# dental-unit-main_v1_0.net
KiCad netlist of a schematic drawn in Altium Designer
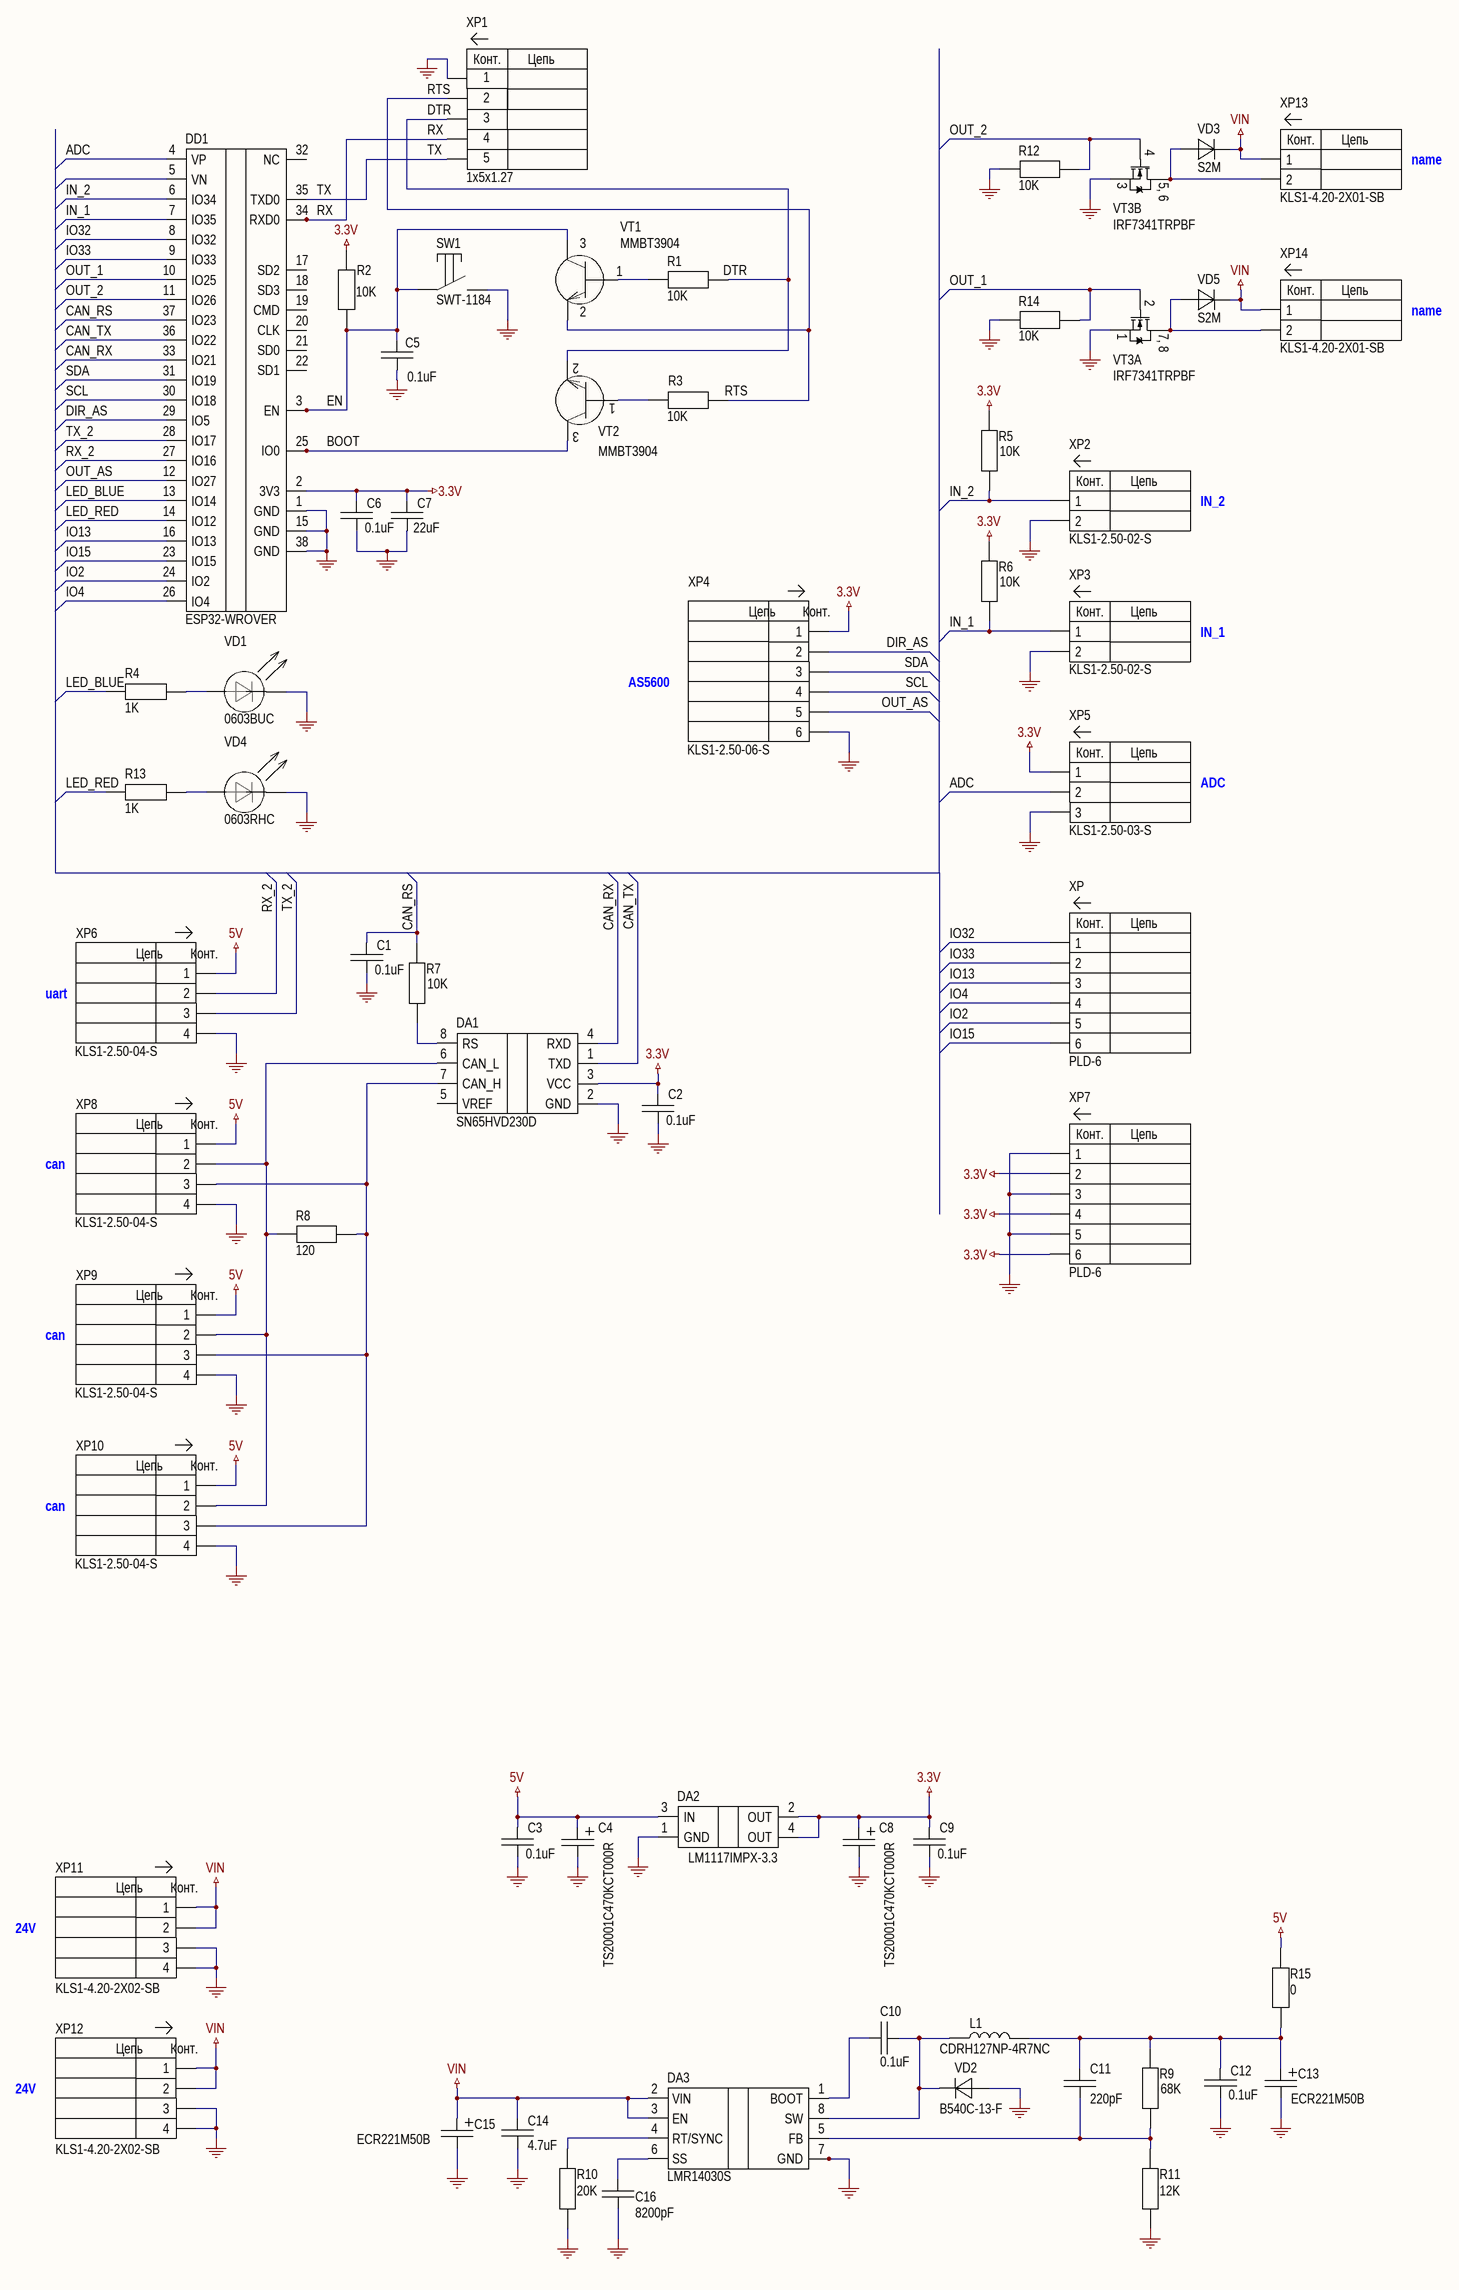
[diagram p0: dental-unit-main v1_0.SchDoc]

(export (version "E")
  (design (tool "Eeschema 10.0.6"))
  (components
    (comp (ref "C1")
      (value "0.1uF")
      (footprint "CC_0603")
      (description "Cap Ceramic, 0603, 0.1u, 10%, 16V, X7R (Yageo)")
      (fields (field (name "Comment") "CC0603KRX7R5BB104"))
      (libsource (lib "my_discrete_new") (part "C"))
    )
    (comp (ref "C2")
      (value "0.1uF")
      (footprint "CC_0603")
      (description "Cap Ceramic, 0603, 0.1u, 10%, 16V, X7R (Yageo)")
      (fields (field (name "Comment") "CC0603KRX7R5BB104"))
      (libsource (lib "my_discrete_new") (part "C"))
    )
    (comp (ref "C3")
      (value "0.1uF")
      (footprint "CC_0603")
      (description "Cap Ceramic, 0603, 0.1u, 10%, 16V, X7R (Yageo)")
      (fields (field (name "Comment") "CC0603KRX7R5BB104"))
      (libsource (lib "my_discrete_new") (part "C"))
    )
    (comp (ref "C4")
      (value "TS20001C470KCT000R")
      (footprint "CC_TANT_C")
      (description "47uF, 16v, C, 10%, @SUNTAN,")
      (libsource (lib "my_discrete_new") (part "C_polar"))
    )
    (comp (ref "C5")
      (value "0.1uF")
      (footprint "CC_0603")
      (description "Cap Ceramic, 0603, 0.1u, 10%, 16V, X7R (Yageo)")
      (fields (field (name "Comment") "CC0603KRX7R5BB104"))
      (libsource (lib "my_discrete_new") (part "C"))
    )
    (comp (ref "C6")
      (value "0.1uF")
      (footprint "CC_0603")
      (description "Cap Ceramic, 0603, 0.1u, 10%, 16V, X7R (Yageo)")
      (fields (field (name "Comment") "CC0603KRX7R5BB104"))
      (libsource (lib "my_discrete_new") (part "C"))
    )
    (comp (ref "C7")
      (value "22uF")
      (footprint "CC_0805")
      (description "Cap Ceramic, 0805, 22u, 20%, 6.3V, X5R, -55 +85C (Murata)")
      (fields (field (name "Comment") "GRM21BR60J226ME39L"))
      (libsource (lib "my_discrete_new") (part "C"))
    )
    (comp (ref "C8")
      (value "TS20001C470KCT000R")
      (footprint "CC_TANT_C")
      (description "47uF, 16v, C, 10%, @SUNTAN,")
      (libsource (lib "my_discrete_new") (part "C_polar"))
    )
    (comp (ref "C9")
      (value "0.1uF")
      (footprint "CC_0603")
      (description "Cap Ceramic, 0603, 0.1u, 10%, 16V, X7R (Yageo)")
      (fields (field (name "Comment") "CC0603KRX7R5BB104"))
      (libsource (lib "my_discrete_new") (part "C"))
    )
    (comp (ref "C10")
      (value "0.1uF")
      (footprint "CC_0805")
      (description "Cap Ceramic, 0805, 0.1u, 5%, 50V, X7R (Yageo)")
      (fields (field (name "Comment") "CC0805JRX7R9BB104"))
      (libsource (lib "my_discrete_new") (part "C"))
    )
    (comp (ref "C11")
      (value "220pF")
      (footprint "CC_0603")
      (description "Cap Ceramic, 0603, 220pF, 10%, 50V, NP0, @YAGEO")
      (fields (field (name "Comment") "CC0603KRX7R9BB221"))
      (libsource (lib "my_discrete_new") (part "C"))
    )
    (comp (ref "C12")
      (value "0.1uF")
      (footprint "CC_0603")
      (description "Cap Ceramic, 0603, 0.1u, 10%, 16V, X7R (Yageo)")
      (fields (field (name "Comment") "CC0603KRX7R5BB104"))
      (libsource (lib "my_discrete_new") (part "C"))
    )
    (comp (ref "C13")
      (value "ECR221M50B")
      (footprint "C_ele_10x13")
      (description "alum. el. Cap, 50v, 220u, 20%, 13x20, @HITANO")
      (libsource (lib "my_discrete_new") (part "C_polar"))
    )
    (comp (ref "C14")
      (value "4.7uF")
      (footprint "CC_0603")
      (description "Cap Ceramic, 0603, 4.7u, 10%, 25V, X5R (Sumsung)")
      (fields (field (name "Comment") "CL10A475KA8NQNC"))
      (libsource (lib "my_discrete_new") (part "C"))
    )
    (comp (ref "C15")
      (value "ECR221M50B")
      (footprint "C_ele_10x13")
      (description "alum. el. Cap, 50v, 220u, 20%, 13x20, @HITANO")
      (libsource (lib "my_discrete_new") (part "C_polar"))
    )
    (comp (ref "C16")
      (value "8200pF")
      (footprint "CC_0603")
      (description "Cap Ceramic, 0603, 8200pF, 10%, 50V, X7R (Yageo)")
      (fields (field (name "Comment") "CC0603KRX7R9BB822"))
      (libsource (lib "my_discrete_new") (part "C"))
    )
    (comp (ref "DA1")
      (value "SN65HVD230D")
      (footprint "SOIC-8")
      (description "3.3-V CAN TRANSCEIVERS, @TI")
      (libsource (lib "my_microschems_new") (part "SN65HVD230D"))
    )
    (comp (ref "DA2")
      (value "LM1117IMPX-3.3")
      (footprint "SOT-223")
      (description "LDO, 3.3v, 0.8A, SOT-223, Texas Instruments")
      (libsource (lib "my_microschems_new") (part "LM1117IMPX-3.3"))
    )
    (comp (ref "DA3")
      (value "LMR14030S")
      (footprint "SOIC-8N")
      (description "DC-DC Step-Down Converter, 40V, 3.5A, @TI")
      (libsource (lib "my_microschems_new") (part "LMR14030S"))
    )
    (comp (ref "DD1")
      (value "ESP32-WROVER")
      (footprint "ESP32-WROVER / WROOM")
      (libsource (lib "my_microschems_new") (part "ESP32-WROVER"))
    )
    (comp (ref "L1")
      (value "CDRH127NP-4R7NC")
      (footprint "CDRH127NP")
      (description "4.7uH, 6.8A, @SUMIDA")
      (libsource (lib "my_discrete_new") (part "L"))
    )
    (comp (ref "R1")
      (value "10K")
      (footprint "RC_0603")
      (description "Res, 0603, 10K, 1%, 0.25W (ф. Yageo)")
      (fields (field (name "POWER") "0.25W") (field (name "Comment") "AC0603FR-0710KL"))
      (libsource (lib "my_discrete_new") (part "R"))
    )
    (comp (ref "R2")
      (value "10K")
      (footprint "RC_0603")
      (description "Res, 0603, 10K, 1%, 0.25W (ф. Yageo)")
      (fields (field (name "POWER") "0.25W") (field (name "Comment") "AC0603FR-0710KL"))
      (libsource (lib "my_discrete_new") (part "R"))
    )
    (comp (ref "R3")
      (value "10K")
      (footprint "RC_0603")
      (description "Res, 0603, 10K, 1%, 0.25W (ф. Yageo)")
      (fields (field (name "POWER") "0.25W") (field (name "Comment") "AC0603FR-0710KL"))
      (libsource (lib "my_discrete_new") (part "R"))
    )
    (comp (ref "R4")
      (value "1K")
      (footprint "RC_0603")
      (description "Res, 0603, 1K 1%, 0.25W (ф. Yageo)")
      (fields (field (name "POWER") "0.25W") (field (name "Comment") "AC0603FR-071KL"))
      (libsource (lib "my_discrete_new") (part "R"))
    )
    (comp (ref "R5")
      (value "10K")
      (footprint "RC_0603")
      (description "Res, 0603, 10K, 1%, 0.25W (ф. Yageo)")
      (fields (field (name "POWER") "0.25W") (field (name "Comment") "AC0603FR-0710KL"))
      (libsource (lib "my_discrete_new") (part "R"))
    )
    (comp (ref "R6")
      (value "10K")
      (footprint "RC_0603")
      (description "Res, 0603, 10K, 1%, 0.25W (ф. Yageo)")
      (fields (field (name "POWER") "0.25W") (field (name "Comment") "AC0603FR-0710KL"))
      (libsource (lib "my_discrete_new") (part "R"))
    )
    (comp (ref "R7")
      (value "10K")
      (footprint "RC_0603")
      (description "Res, 0603, 10K, 1%, 0.25W (ф. Yageo)")
      (fields (field (name "POWER") "0.25W") (field (name "Comment") "AC0603FR-0710KL"))
      (libsource (lib "my_discrete_new") (part "R"))
    )
    (comp (ref "R8")
      (value "120")
      (footprint "RC_0603")
      (description "Res, 0603, 120, 1%, 0.25W (ф. Yageo)")
      (fields (field (name "POWER") "0.25W") (field (name "Comment") "RC0603FR-07120RL"))
      (libsource (lib "my_discrete_new") (part "R"))
    )
    (comp (ref "R9")
      (value "68K")
      (footprint "RC_0603")
      (description "Res, 0603, 68K, 1%, 0.25W (ф. Yageo)")
      (fields (field (name "POWER") "0.25W") (field (name "Comment") "RC0603FR-0768KL"))
      (libsource (lib "my_discrete_new") (part "R"))
    )
    (comp (ref "R10")
      (value "20K")
      (footprint "RC_0603")
      (description "Res, 0603, 20K, 1%, 0.25W (ф. Yageo)")
      (fields (field (name "POWER") "0.25W") (field (name "Comment") "RC0603FR-0720KL"))
      (libsource (lib "my_discrete_new") (part "R"))
    )
    (comp (ref "R11")
      (value "12K")
      (footprint "RC_0603")
      (description "Res, 0603, 12K, 1%, 0.25W (ф. Yageo)")
      (fields (field (name "POWER") "0.25W") (field (name "Comment") "RC0603FR-0712KL"))
      (libsource (lib "my_discrete_new") (part "R"))
    )
    (comp (ref "R12")
      (value "10K")
      (footprint "RC_0603")
      (description "Res, 0603, 10K, 1%, 0.25W (ф. Yageo)")
      (fields (field (name "POWER") "0.25W") (field (name "Comment") "AC0603FR-0710KL"))
      (libsource (lib "my_discrete_new") (part "R"))
    )
    (comp (ref "R13")
      (value "1K")
      (footprint "RC_0603")
      (description "Res, 0603, 1K 1%, 0.25W (ф. Yageo)")
      (fields (field (name "POWER") "0.25W") (field (name "Comment") "AC0603FR-071KL"))
      (libsource (lib "my_discrete_new") (part "R"))
    )
    (comp (ref "R14")
      (value "10K")
      (footprint "RC_0603")
      (description "Res, 0603, 10K, 1%, 0.25W (ф. Yageo)")
      (fields (field (name "POWER") "0.25W") (field (name "Comment") "AC0603FR-0710KL"))
      (libsource (lib "my_discrete_new") (part "R"))
    )
    (comp (ref "R15")
      (value "0")
      (footprint "RC_0603")
      (description "Res, 0603, 0, 1%, 0.25W (ф. Yageo)")
      (fields (field (name "POWER") "0.25W") (field (name "Comment") "AC0603FR-070RL"))
      (libsource (lib "my_discrete_new") (part "R"))
    )
    (comp (ref "SW1")
      (value "SWT-1184")
      (footprint "IT-1184")
      (libsource (lib "my_discrete_new") (part "smd-side-push-button"))
    )
    (comp (ref "VD1")
      (value "0603BUC")
      (footprint "LED_0603")
      (description "Led, 0603, BLUE, 20mA, 125, 140MCD, CPMELEC")
      (libsource (lib "my_discrete_new") (part "LED"))
    )
    (comp (ref "VD2")
      (value "B540C-13-F")
      (footprint "DO-214AB(SMC)")
      (libsource (lib "my_discrete_new") (part "D"))
    )
    (comp (ref "VD3")
      (value "S2M")
      (footprint "DO-214AA(SMB)")
      (description "1000В, 2А, 2,5мкс, SMB, @DIODES")
      (libsource (lib "my_discrete_new") (part "D"))
    )
    (comp (ref "VD4")
      (value "0603RHC")
      (footprint "LED_0603")
      (description "Led, 0603, RED, 20mA, 125, 140MCD, CPMELEC")
      (libsource (lib "my_discrete_new") (part "LED"))
    )
    (comp (ref "VD5")
      (value "S2M")
      (footprint "DO-214AA(SMB)")
      (description "1000В, 2А, 2,5мкс, SMB, @DIODES")
      (libsource (lib "my_discrete_new") (part "D"))
    )
    (comp (ref "VT1")
      (value "MMBT3904")
      (footprint "SOT-23-3")
      (libsource (lib "my_microschems_new") (part "N-P-N-SOT-23"))
    )
    (comp (ref "VT2")
      (value "MMBT3904")
      (footprint "SOT-23-3")
      (libsource (lib "my_microschems_new") (part "N-P-N-SOT-23"))
    )
    (comp (ref "VT3")
      (value "IRF7341TRPBF")
      (footprint "SOIC-8")
      (description "HEXFET Power MOSFET, Dual N-Channel Mosfet, 55 В, 4.7 А, 2 Вт, @INFIN")
      (libsource (lib "my_microschems_new") (part "IRF7341TRPBF"))
    )
    (comp (ref "XP")
      (value "PLD-6")
      (footprint "PLD-6")
      (libsource (lib "my_connectors_new") (part "XT_PLD-6"))
    )
    (comp (ref "XP1")
      (value "1x5x1.27")
      (footprint "XT_1x5x1.27_offset")
      (libsource (lib "my_connectors_new") (part "XT_1x5x1_27"))
    )
    (comp (ref "XP2")
      (value "KLS1-2.50-02-S")
      (footprint "KLS1-2.50-02-S")
      (description "2.5mm, 2pin, KLS")
      (fields (field (name "NAME") "IN_2"))
      (libsource (lib "my_connectors_new") (part "KLS1-2.50-02-x"))
    )
    (comp (ref "XP3")
      (value "KLS1-2.50-02-S")
      (footprint "KLS1-2.50-02-S")
      (description "2.5mm, 2pin, KLS")
      (fields (field (name "NAME") "IN_1"))
      (libsource (lib "my_connectors_new") (part "KLS1-2.50-02-x"))
    )
    (comp (ref "XP4")
      (value "KLS1-2.50-06-S")
      (footprint "KLS1-2.50-06-S")
      (description "2.5mm, 6pin, KLS")
      (fields (field (name "NAME") "AS5600"))
      (libsource (lib "my_connectors_new") (part "KLS1-2.50-06-x"))
    )
    (comp (ref "XP5")
      (value "KLS1-2.50-03-S")
      (footprint "KLS1-2.50-03-S")
      (description "2.5mm, 3pin, KLS")
      (fields (field (name "NAME") "ADC"))
      (libsource (lib "my_connectors_new") (part "KLS1-2.50-03-x"))
    )
    (comp (ref "XP6")
      (value "KLS1-2.50-04-S")
      (footprint "KLS1-2.50-04-S")
      (description "2.5mm, 4pin, KLS")
      (fields (field (name "NAME") "uart"))
      (libsource (lib "my_connectors_new") (part "KLS1-2.50-04-x"))
    )
    (comp (ref "XP7")
      (value "PLD-6")
      (footprint "PLD-6")
      (libsource (lib "my_connectors_new") (part "XT_PLD-6"))
    )
    (comp (ref "XP8")
      (value "KLS1-2.50-04-S")
      (footprint "KLS1-2.50-04-S")
      (description "2.5mm, 4pin, KLS")
      (fields (field (name "NAME") "can"))
      (libsource (lib "my_connectors_new") (part "KLS1-2.50-04-x"))
    )
    (comp (ref "XP9")
      (value "KLS1-2.50-04-S")
      (footprint "KLS1-2.50-04-S")
      (description "2.5mm, 4pin, KLS")
      (fields (field (name "NAME") "can"))
      (libsource (lib "my_connectors_new") (part "KLS1-2.50-04-x"))
    )
    (comp (ref "XP10")
      (value "KLS1-2.50-04-S")
      (footprint "KLS1-2.50-04-S")
      (description "2.5mm, 4pin, KLS")
      (fields (field (name "NAME") "can"))
      (libsource (lib "my_connectors_new") (part "KLS1-2.50-04-x"))
    )
    (comp (ref "XP11")
      (value "KLS1-4.20-2X02-SB")
      (footprint "KLS1-4.20-2X02-SB")
      (description "4.2mm, 4pin, KLS")
      (fields (field (name "NAME") "24V"))
      (libsource (lib "my_connectors_new") (part "KLS1-4.20-2X02-x"))
    )
    (comp (ref "XP12")
      (value "KLS1-4.20-2X02-SB")
      (footprint "KLS1-4.20-2X02-SB")
      (description "4.2mm, 4pin, KLS")
      (fields (field (name "NAME") "24V"))
      (libsource (lib "my_connectors_new") (part "KLS1-4.20-2X02-x"))
    )
    (comp (ref "XP13")
      (value "KLS1-4.20-2X01-SB")
      (footprint "KLS1-4.20-2X01-SB")
      (description "4.2mm, 2pin, KLS")
      (fields (field (name "NAME") "name"))
      (libsource (lib "my_connectors_new") (part "KLS1-4.20-2X01-x"))
    )
    (comp (ref "XP14")
      (value "KLS1-4.20-2X01-SB")
      (footprint "KLS1-4.20-2X01-SB")
      (description "4.2mm, 2pin, KLS")
      (fields (field (name "NAME") "name"))
      (libsource (lib "my_connectors_new") (part "KLS1-4.20-2X01-x"))
    )
  )
  (nets
    (net (code "1") (name "/ADC") (class "Default")
      (node (ref "DD1") (pin "4") (pinfunction "VP_4") (pintype "passive"))
      (node (ref "XP5") (pin "2") (pinfunction "2_2") (pintype "passive"))
    )
    (net (code "2") (name "/BOOT") (class "Default")
      (node (ref "DD1") (pin "25") (pinfunction "IO0_25") (pintype "passive"))
      (node (ref "VT2") (pin "3") (pinfunction "C_3") (pintype "passive"))
    )
    (net (code "3") (name "/CAN_RS") (class "Default")
      (node (ref "C1") (pin "2") (pinfunction "2_2") (pintype "passive"))
      (node (ref "DD1") (pin "37") (pinfunction "IO23_37") (pintype "passive"))
      (node (ref "R7") (pin "2") (pinfunction "2_2") (pintype "passive"))
    )
    (net (code "4") (name "/CAN_RX") (class "Default")
      (node (ref "DA1") (pin "4") (pinfunction "RXD_4") (pintype "power_in"))
      (node (ref "DD1") (pin "33") (pinfunction "IO21_33") (pintype "passive"))
    )
    (net (code "5") (name "/CAN_TX") (class "Default")
      (node (ref "DA1") (pin "1") (pinfunction "TXD_1") (pintype "passive"))
      (node (ref "DD1") (pin "36") (pinfunction "IO22_36") (pintype "passive"))
    )
    (net (code "6") (name "/DIR_AS") (class "Default")
      (node (ref "DD1") (pin "29") (pinfunction "IO5_29") (pintype "passive"))
      (node (ref "XP4") (pin "2") (pinfunction "2_2") (pintype "passive"))
    )
    (net (code "7") (name "/DTR") (class "Default")
      (node (ref "R1") (pin "2") (pinfunction "2_2") (pintype "passive"))
      (node (ref "VT2") (pin "2") (pinfunction "E_2") (pintype "passive"))
      (node (ref "XP1") (pin "3") (pinfunction "3_3") (pintype "passive"))
    )
    (net (code "8") (name "/EN") (class "Default")
      (node (ref "C5") (pin "2") (pinfunction "2_2") (pintype "passive"))
      (node (ref "DD1") (pin "3") (pinfunction "EN_3") (pintype "passive"))
      (node (ref "R2") (pin "1") (pinfunction "1_1") (pintype "passive"))
      (node (ref "SW1") (pin "1") (pinfunction "1_1") (pintype "passive"))
      (node (ref "VT1") (pin "3") (pinfunction "C_3") (pintype "passive"))
    )
    (net (code "9") (name "/IN_1") (class "Default")
      (node (ref "DD1") (pin "7") (pinfunction "IO35_7") (pintype "passive"))
      (node (ref "R6") (pin "1") (pinfunction "1_1") (pintype "passive"))
      (node (ref "XP3") (pin "1") (pinfunction "1_1") (pintype "passive"))
    )
    (net (code "10") (name "/IN_2") (class "Default")
      (node (ref "DD1") (pin "6") (pinfunction "IO34_6") (pintype "passive"))
      (node (ref "R5") (pin "1") (pinfunction "1_1") (pintype "passive"))
      (node (ref "XP2") (pin "1") (pinfunction "1_1") (pintype "passive"))
    )
    (net (code "11") (name "/IO2") (class "Default")
      (node (ref "DD1") (pin "24") (pinfunction "IO2_24") (pintype "passive"))
      (node (ref "XP") (pin "5") (pinfunction "5_5") (pintype "passive"))
    )
    (net (code "12") (name "/IO4") (class "Default")
      (node (ref "DD1") (pin "26") (pinfunction "IO4_26") (pintype "passive"))
      (node (ref "XP") (pin "4") (pinfunction "4_4") (pintype "passive"))
    )
    (net (code "13") (name "/IO13") (class "Default")
      (node (ref "DD1") (pin "16") (pinfunction "IO13_16") (pintype "passive"))
      (node (ref "XP") (pin "3") (pinfunction "3_3") (pintype "passive"))
    )
    (net (code "14") (name "/IO15") (class "Default")
      (node (ref "DD1") (pin "23") (pinfunction "IO15_23") (pintype "passive"))
      (node (ref "XP") (pin "6") (pinfunction "6_6") (pintype "passive"))
    )
    (net (code "15") (name "/IO32") (class "Default")
      (node (ref "DD1") (pin "8") (pinfunction "IO32_8") (pintype "power_in"))
      (node (ref "XP") (pin "1") (pinfunction "1_1") (pintype "passive"))
    )
    (net (code "16") (name "/IO33") (class "Default")
      (node (ref "DD1") (pin "9") (pinfunction "IO33_9") (pintype "passive"))
      (node (ref "XP") (pin "2") (pinfunction "2_2") (pintype "passive"))
    )
    (net (code "17") (name "/LED_BLUE") (class "Default")
      (node (ref "DD1") (pin "13") (pinfunction "IO14_13") (pintype "passive"))
      (node (ref "R4") (pin "1") (pinfunction "1_1") (pintype "passive"))
    )
    (net (code "18") (name "/LED_RED") (class "Default")
      (node (ref "DD1") (pin "14") (pinfunction "IO12_14") (pintype "passive"))
      (node (ref "R13") (pin "1") (pinfunction "1_1") (pintype "passive"))
    )
    (net (code "19") (name "/OUT_1") (class "Default")
      (node (ref "DD1") (pin "10") (pinfunction "IO25_10") (pintype "passive"))
      (node (ref "R14") (pin "1") (pinfunction "1_1") (pintype "passive"))
      (node (ref "VT3") (pin "2") (pinfunction "G_2") (pintype "passive"))
    )
    (net (code "20") (name "/OUT_2") (class "Default")
      (node (ref "DD1") (pin "11") (pinfunction "IO26_11") (pintype "passive"))
      (node (ref "R12") (pin "1") (pinfunction "1_1") (pintype "passive"))
      (node (ref "VT3") (pin "4") (pinfunction "G_4") (pintype "passive"))
    )
    (net (code "21") (name "/OUT_AS") (class "Default")
      (node (ref "DD1") (pin "12") (pinfunction "IO27_12") (pintype "passive"))
      (node (ref "XP4") (pin "5") (pinfunction "5_5") (pintype "passive"))
    )
    (net (code "22") (name "/RTS") (class "Default")
      (node (ref "R3") (pin "2") (pinfunction "2_2") (pintype "passive"))
      (node (ref "VT1") (pin "2") (pinfunction "E_2") (pintype "passive"))
      (node (ref "XP1") (pin "2") (pinfunction "2_2") (pintype "passive"))
    )
    (net (code "23") (name "/RX") (class "Default")
      (node (ref "DD1") (pin "34") (pinfunction "RXD0_34") (pintype "passive"))
      (node (ref "XP1") (pin "4") (pinfunction "4_4") (pintype "passive"))
    )
    (net (code "24") (name "/RX_2") (class "Default")
      (node (ref "DD1") (pin "27") (pinfunction "IO16_27") (pintype "passive"))
      (node (ref "XP6") (pin "2") (pinfunction "2_2") (pintype "passive"))
    )
    (net (code "25") (name "/SCL") (class "Default")
      (node (ref "DD1") (pin "30") (pinfunction "IO18_30") (pintype "passive"))
      (node (ref "XP4") (pin "4") (pinfunction "4_4") (pintype "passive"))
    )
    (net (code "26") (name "/SDA") (class "Default")
      (node (ref "DD1") (pin "31") (pinfunction "IO19_31") (pintype "passive"))
      (node (ref "XP4") (pin "3") (pinfunction "3_3") (pintype "passive"))
    )
    (net (code "27") (name "/TX") (class "Default")
      (node (ref "DD1") (pin "35") (pinfunction "TXD0_35") (pintype "passive"))
      (node (ref "XP1") (pin "5") (pinfunction "5_5") (pintype "passive"))
    )
    (net (code "28") (name "/TX_2") (class "Default")
      (node (ref "DD1") (pin "28") (pinfunction "IO17_28") (pintype "passive"))
      (node (ref "XP6") (pin "3") (pinfunction "3_3") (pintype "passive"))
    )
    (net (code "29") (name "3.3V") (class "Default")
      (node (ref "C2") (pin "2") (pinfunction "2_2") (pintype "passive"))
      (node (ref "C6") (pin "2") (pinfunction "2_2") (pintype "passive"))
      (node (ref "C7") (pin "2") (pinfunction "2_2") (pintype "passive"))
      (node (ref "C8") (pin "1") (pinfunction "1_1") (pintype "passive"))
      (node (ref "C9") (pin "2") (pinfunction "2_2") (pintype "passive"))
      (node (ref "DA1") (pin "3") (pinfunction "VCC_3") (pintype "passive"))
      (node (ref "DA2") (pin "2") (pinfunction "OUT_2") (pintype "power_in"))
      (node (ref "DA2") (pin "4") (pinfunction "OUT_4") (pintype "power_in"))
      (node (ref "DD1") (pin "2") (pinfunction "3V3_2") (pintype "power_in"))
      (node (ref "R2") (pin "2") (pinfunction "2_2") (pintype "passive"))
      (node (ref "R5") (pin "2") (pinfunction "2_2") (pintype "passive"))
      (node (ref "R6") (pin "2") (pinfunction "2_2") (pintype "passive"))
      (node (ref "XP4") (pin "1") (pinfunction "1_1") (pintype "passive"))
      (node (ref "XP5") (pin "1") (pinfunction "1_1") (pintype "passive"))
      (node (ref "XP7") (pin "2") (pinfunction "2_2") (pintype "passive"))
      (node (ref "XP7") (pin "4") (pinfunction "4_4") (pintype "passive"))
      (node (ref "XP7") (pin "6") (pinfunction "6_6") (pintype "passive"))
    )
    (net (code "30") (name "5V") (class "Default")
      (node (ref "C3") (pin "2") (pinfunction "2_2") (pintype "passive"))
      (node (ref "C4") (pin "1") (pinfunction "1_1") (pintype "passive"))
      (node (ref "DA2") (pin "3") (pinfunction "IN_3") (pintype "passive"))
      (node (ref "R15") (pin "2") (pinfunction "2_2") (pintype "passive"))
      (node (ref "XP10") (pin "1") (pinfunction "1_1") (pintype "passive"))
      (node (ref "XP6") (pin "1") (pinfunction "1_1") (pintype "passive"))
      (node (ref "XP8") (pin "1") (pinfunction "1_1") (pintype "passive"))
      (node (ref "XP9") (pin "1") (pinfunction "1_1") (pintype "passive"))
    )
    (net (code "31") (name "GND") (class "Default")
      (node (ref "C1") (pin "1") (pinfunction "1_1") (pintype "passive"))
      (node (ref "C12") (pin "1") (pinfunction "1_1") (pintype "passive"))
      (node (ref "C13") (pin "2") (pinfunction "2_2") (pintype "passive"))
      (node (ref "C14") (pin "1") (pinfunction "1_1") (pintype "passive"))
      (node (ref "C15") (pin "2") (pinfunction "2_2") (pintype "passive"))
      (node (ref "C16") (pin "2") (pinfunction "2_2") (pintype "passive"))
      (node (ref "C2") (pin "1") (pinfunction "1_1") (pintype "passive"))
      (node (ref "C3") (pin "1") (pinfunction "1_1") (pintype "passive"))
      (node (ref "C4") (pin "2") (pinfunction "2_2") (pintype "passive"))
      (node (ref "C5") (pin "1") (pinfunction "1_1") (pintype "passive"))
      (node (ref "C6") (pin "1") (pinfunction "1_1") (pintype "passive"))
      (node (ref "C7") (pin "1") (pinfunction "1_1") (pintype "passive"))
      (node (ref "C8") (pin "2") (pinfunction "2_2") (pintype "passive"))
      (node (ref "C9") (pin "1") (pinfunction "1_1") (pintype "passive"))
      (node (ref "DA1") (pin "2") (pinfunction "GND_2") (pintype "passive"))
      (node (ref "DA2") (pin "1") (pinfunction "GND_1") (pintype "passive"))
      (node (ref "DA3") (pin "7") (pinfunction "GND_7") (pintype "passive"))
      (node (ref "DA3") (pin "9") (pinfunction "9_9") (pintype "passive"))
      (node (ref "DD1") (pin "1") (pinfunction "GND_1") (pintype "power_in"))
      (node (ref "DD1") (pin "15") (pinfunction "GND_15") (pintype "power_in"))
      (node (ref "DD1") (pin "38") (pinfunction "GND_38") (pintype "power_in"))
      (node (ref "DD1") (pin "39") (pinfunction "GND_39") (pintype "power_in"))
      (node (ref "R10") (pin "1") (pinfunction "1_1") (pintype "passive"))
      (node (ref "R11") (pin "1") (pinfunction "1_1") (pintype "passive"))
      (node (ref "R12") (pin "2") (pinfunction "2_2") (pintype "passive"))
      (node (ref "R14") (pin "2") (pinfunction "2_2") (pintype "passive"))
      (node (ref "SW1") (pin "2") (pinfunction "2_2") (pintype "passive"))
      (node (ref "VD1") (pin "2") (pinfunction "C_2") (pintype "passive"))
      (node (ref "VD2") (pin "1") (pinfunction "A_1") (pintype "passive"))
      (node (ref "VD4") (pin "2") (pinfunction "C_2") (pintype "passive"))
      (node (ref "VT3") (pin "1") (pinfunction "S_1") (pintype "passive"))
      (node (ref "VT3") (pin "3") (pinfunction "S_3") (pintype "passive"))
      (node (ref "XP1") (pin "1") (pinfunction "1_1") (pintype "passive"))
      (node (ref "XP10") (pin "4") (pinfunction "4_4") (pintype "passive"))
      (node (ref "XP11") (pin "3") (pinfunction "3_3") (pintype "passive"))
      (node (ref "XP11") (pin "4") (pinfunction "4_4") (pintype "passive"))
      (node (ref "XP12") (pin "3") (pinfunction "3_3") (pintype "passive"))
      (node (ref "XP12") (pin "4") (pinfunction "4_4") (pintype "passive"))
      (node (ref "XP2") (pin "2") (pinfunction "2_2") (pintype "passive"))
      (node (ref "XP3") (pin "2") (pinfunction "2_2") (pintype "passive"))
      (node (ref "XP4") (pin "6") (pinfunction "6_6") (pintype "passive"))
      (node (ref "XP5") (pin "3") (pinfunction "3_3") (pintype "passive"))
      (node (ref "XP6") (pin "4") (pinfunction "4_4") (pintype "passive"))
      (node (ref "XP7") (pin "1") (pinfunction "1_1") (pintype "passive"))
      (node (ref "XP7") (pin "3") (pinfunction "3_3") (pintype "passive"))
      (node (ref "XP7") (pin "5") (pinfunction "5_5") (pintype "passive"))
      (node (ref "XP8") (pin "4") (pinfunction "4_4") (pintype "passive"))
      (node (ref "XP9") (pin "4") (pinfunction "4_4") (pintype "passive"))
    )
    (net (code "32") (name "Net-(C11-Pad1)") (class "Default")
      (node (ref "C11") (pin "1") (pinfunction "1_1") (pintype "passive"))
      (node (ref "C12") (pin "2") (pinfunction "2_2") (pintype "passive"))
      (node (ref "C13") (pin "1") (pinfunction "1_1") (pintype "passive"))
      (node (ref "L1") (pin "2") (pinfunction "2_2") (pintype "passive"))
      (node (ref "R15") (pin "1") (pinfunction "1_1") (pintype "passive"))
      (node (ref "R9") (pin "2") (pinfunction "2_2") (pintype "passive"))
    )
    (net (code "33") (name "Net-(DA1-CAN_H)") (class "Default")
      (node (ref "DA1") (pin "7") (pinfunction "CAN_H_7") (pintype "passive"))
      (node (ref "R8") (pin "1") (pinfunction "1_1") (pintype "passive"))
      (node (ref "XP10") (pin "3") (pinfunction "3_3") (pintype "passive"))
      (node (ref "XP8") (pin "3") (pinfunction "3_3") (pintype "passive"))
      (node (ref "XP9") (pin "3") (pinfunction "3_3") (pintype "passive"))
    )
    (net (code "34") (name "Net-(DA1-CAN_L)") (class "Default")
      (node (ref "DA1") (pin "6") (pinfunction "CAN_L_6") (pintype "passive"))
      (node (ref "R8") (pin "2") (pinfunction "2_2") (pintype "passive"))
      (node (ref "XP10") (pin "2") (pinfunction "2_2") (pintype "passive"))
      (node (ref "XP8") (pin "2") (pinfunction "2_2") (pintype "passive"))
      (node (ref "XP9") (pin "2") (pinfunction "2_2") (pintype "passive"))
    )
    (net (code "35") (name "Net-(DA1-RS)") (class "Default")
      (node (ref "DA1") (pin "8") (pinfunction "RS_8") (pintype "power_in"))
      (node (ref "R7") (pin "1") (pinfunction "1_1") (pintype "passive"))
    )
    (net (code "36") (name "Net-(DA3-BOOT)") (class "Default")
      (node (ref "C10") (pin "2") (pinfunction "2_2") (pintype "passive"))
      (node (ref "DA3") (pin "1") (pinfunction "BOOT_1") (pintype "passive"))
    )
    (net (code "37") (name "Net-(DA3-FB)") (class "Default")
      (node (ref "C11") (pin "2") (pinfunction "2_2") (pintype "passive"))
      (node (ref "DA3") (pin "5") (pinfunction "FB_5") (pintype "passive"))
      (node (ref "R11") (pin "2") (pinfunction "2_2") (pintype "passive"))
      (node (ref "R9") (pin "1") (pinfunction "1_1") (pintype "passive"))
    )
    (net (code "38") (name "Net-(DA3-RT{slash}SYNC)") (class "Default")
      (node (ref "DA3") (pin "4") (pinfunction "RT/SYNC_4") (pintype "passive"))
      (node (ref "R10") (pin "2") (pinfunction "2_2") (pintype "passive"))
    )
    (net (code "39") (name "Net-(DA3-SS)") (class "Default")
      (node (ref "C16") (pin "1") (pinfunction "1_1") (pintype "passive"))
      (node (ref "DA3") (pin "6") (pinfunction "SS_6") (pintype "passive"))
    )
    (net (code "40") (name "Net-(DA3-SW)") (class "Default")
      (node (ref "C10") (pin "1") (pinfunction "1_1") (pintype "passive"))
      (node (ref "DA3") (pin "8") (pinfunction "SW_8") (pintype "passive"))
      (node (ref "L1") (pin "1") (pinfunction "1_1") (pintype "passive"))
      (node (ref "VD2") (pin "2") (pinfunction "C_2") (pintype "passive"))
    )
    (net (code "41") (name "Net-(VD1-A)") (class "Default")
      (node (ref "R4") (pin "2") (pinfunction "2_2") (pintype "passive"))
      (node (ref "VD1") (pin "1") (pinfunction "A_1") (pintype "passive"))
    )
    (net (code "42") (name "Net-(VD3-A)") (class "Default")
      (node (ref "VD3") (pin "1") (pinfunction "A_1") (pintype "passive"))
      (node (ref "VT3") (pin "5") (pinfunction "D_5") (pintype "passive"))
      (node (ref "VT3") (pin "6") (pinfunction "D_6") (pintype "passive"))
      (node (ref "XP13") (pin "2") (pinfunction "2_2") (pintype "passive"))
    )
    (net (code "43") (name "Net-(VD4-A)") (class "Default")
      (node (ref "R13") (pin "2") (pinfunction "2_2") (pintype "passive"))
      (node (ref "VD4") (pin "1") (pinfunction "A_1") (pintype "passive"))
    )
    (net (code "44") (name "Net-(VD5-A)") (class "Default")
      (node (ref "VD5") (pin "1") (pinfunction "A_1") (pintype "passive"))
      (node (ref "VT3") (pin "7") (pinfunction "D_7") (pintype "passive"))
      (node (ref "VT3") (pin "8") (pinfunction "D_8") (pintype "passive"))
      (node (ref "XP14") (pin "2") (pinfunction "2_2") (pintype "passive"))
    )
    (net (code "45") (name "Net-(VT1-B)") (class "Default")
      (node (ref "R1") (pin "1") (pinfunction "1_1") (pintype "passive"))
      (node (ref "VT1") (pin "1") (pinfunction "B_1") (pintype "passive"))
    )
    (net (code "46") (name "Net-(VT2-B)") (class "Default")
      (node (ref "R3") (pin "1") (pinfunction "1_1") (pintype "passive"))
      (node (ref "VT2") (pin "1") (pinfunction "B_1") (pintype "passive"))
    )
    (net (code "47") (name "VIN") (class "Default")
      (node (ref "C14") (pin "2") (pinfunction "2_2") (pintype "passive"))
      (node (ref "C15") (pin "1") (pinfunction "1_1") (pintype "passive"))
      (node (ref "DA3") (pin "2") (pinfunction "VIN_2") (pintype "passive"))
      (node (ref "DA3") (pin "3") (pinfunction "EN_3") (pintype "passive"))
      (node (ref "VD3") (pin "2") (pinfunction "C_2") (pintype "passive"))
      (node (ref "VD5") (pin "2") (pinfunction "C_2") (pintype "passive"))
      (node (ref "XP11") (pin "1") (pinfunction "1_1") (pintype "passive"))
      (node (ref "XP11") (pin "2") (pinfunction "2_2") (pintype "passive"))
      (node (ref "XP12") (pin "1") (pinfunction "1_1") (pintype "passive"))
      (node (ref "XP12") (pin "2") (pinfunction "2_2") (pintype "passive"))
      (node (ref "XP13") (pin "1") (pinfunction "1_1") (pintype "passive"))
      (node (ref "XP14") (pin "1") (pinfunction "1_1") (pintype "passive"))
    )
    (net (code "48") (name "unconnected-(DA1-VREF-Pad5)") (class "Default")
      (node (ref "DA1") (pin "5") (pinfunction "VREF_5") (pintype "passive"))
    )
    (net (code "49") (name "unconnected-(DD1-CLK-Pad20)") (class "Default")
      (node (ref "DD1") (pin "20") (pinfunction "CLK_20") (pintype "passive"))
    )
    (net (code "50") (name "unconnected-(DD1-CMD-Pad19)") (class "Default")
      (node (ref "DD1") (pin "19") (pinfunction "CMD_19") (pintype "passive"))
    )
    (net (code "51") (name "unconnected-(DD1-NC-Pad32)") (class "Default")
      (node (ref "DD1") (pin "32") (pinfunction "NC_32") (pintype "passive"))
    )
    (net (code "52") (name "unconnected-(DD1-SD0-Pad21)") (class "Default")
      (node (ref "DD1") (pin "21") (pinfunction "SD0_21") (pintype "passive"))
    )
    (net (code "53") (name "unconnected-(DD1-SD1-Pad22)") (class "Default")
      (node (ref "DD1") (pin "22") (pinfunction "SD1_22") (pintype "passive"))
    )
    (net (code "54") (name "unconnected-(DD1-SD2-Pad17)") (class "Default")
      (node (ref "DD1") (pin "17") (pinfunction "SD2_17") (pintype "passive"))
    )
    (net (code "55") (name "unconnected-(DD1-SD3-Pad18)") (class "Default")
      (node (ref "DD1") (pin "18") (pinfunction "SD3_18") (pintype "passive"))
    )
    (net (code "56") (name "unconnected-(DD1-VN-Pad5)") (class "Default")
      (node (ref "DD1") (pin "5") (pinfunction "VN_5") (pintype "passive"))
    )
  )
)
